# H17R10.net
KiCad netlist of a schematic drawn in EAGLE
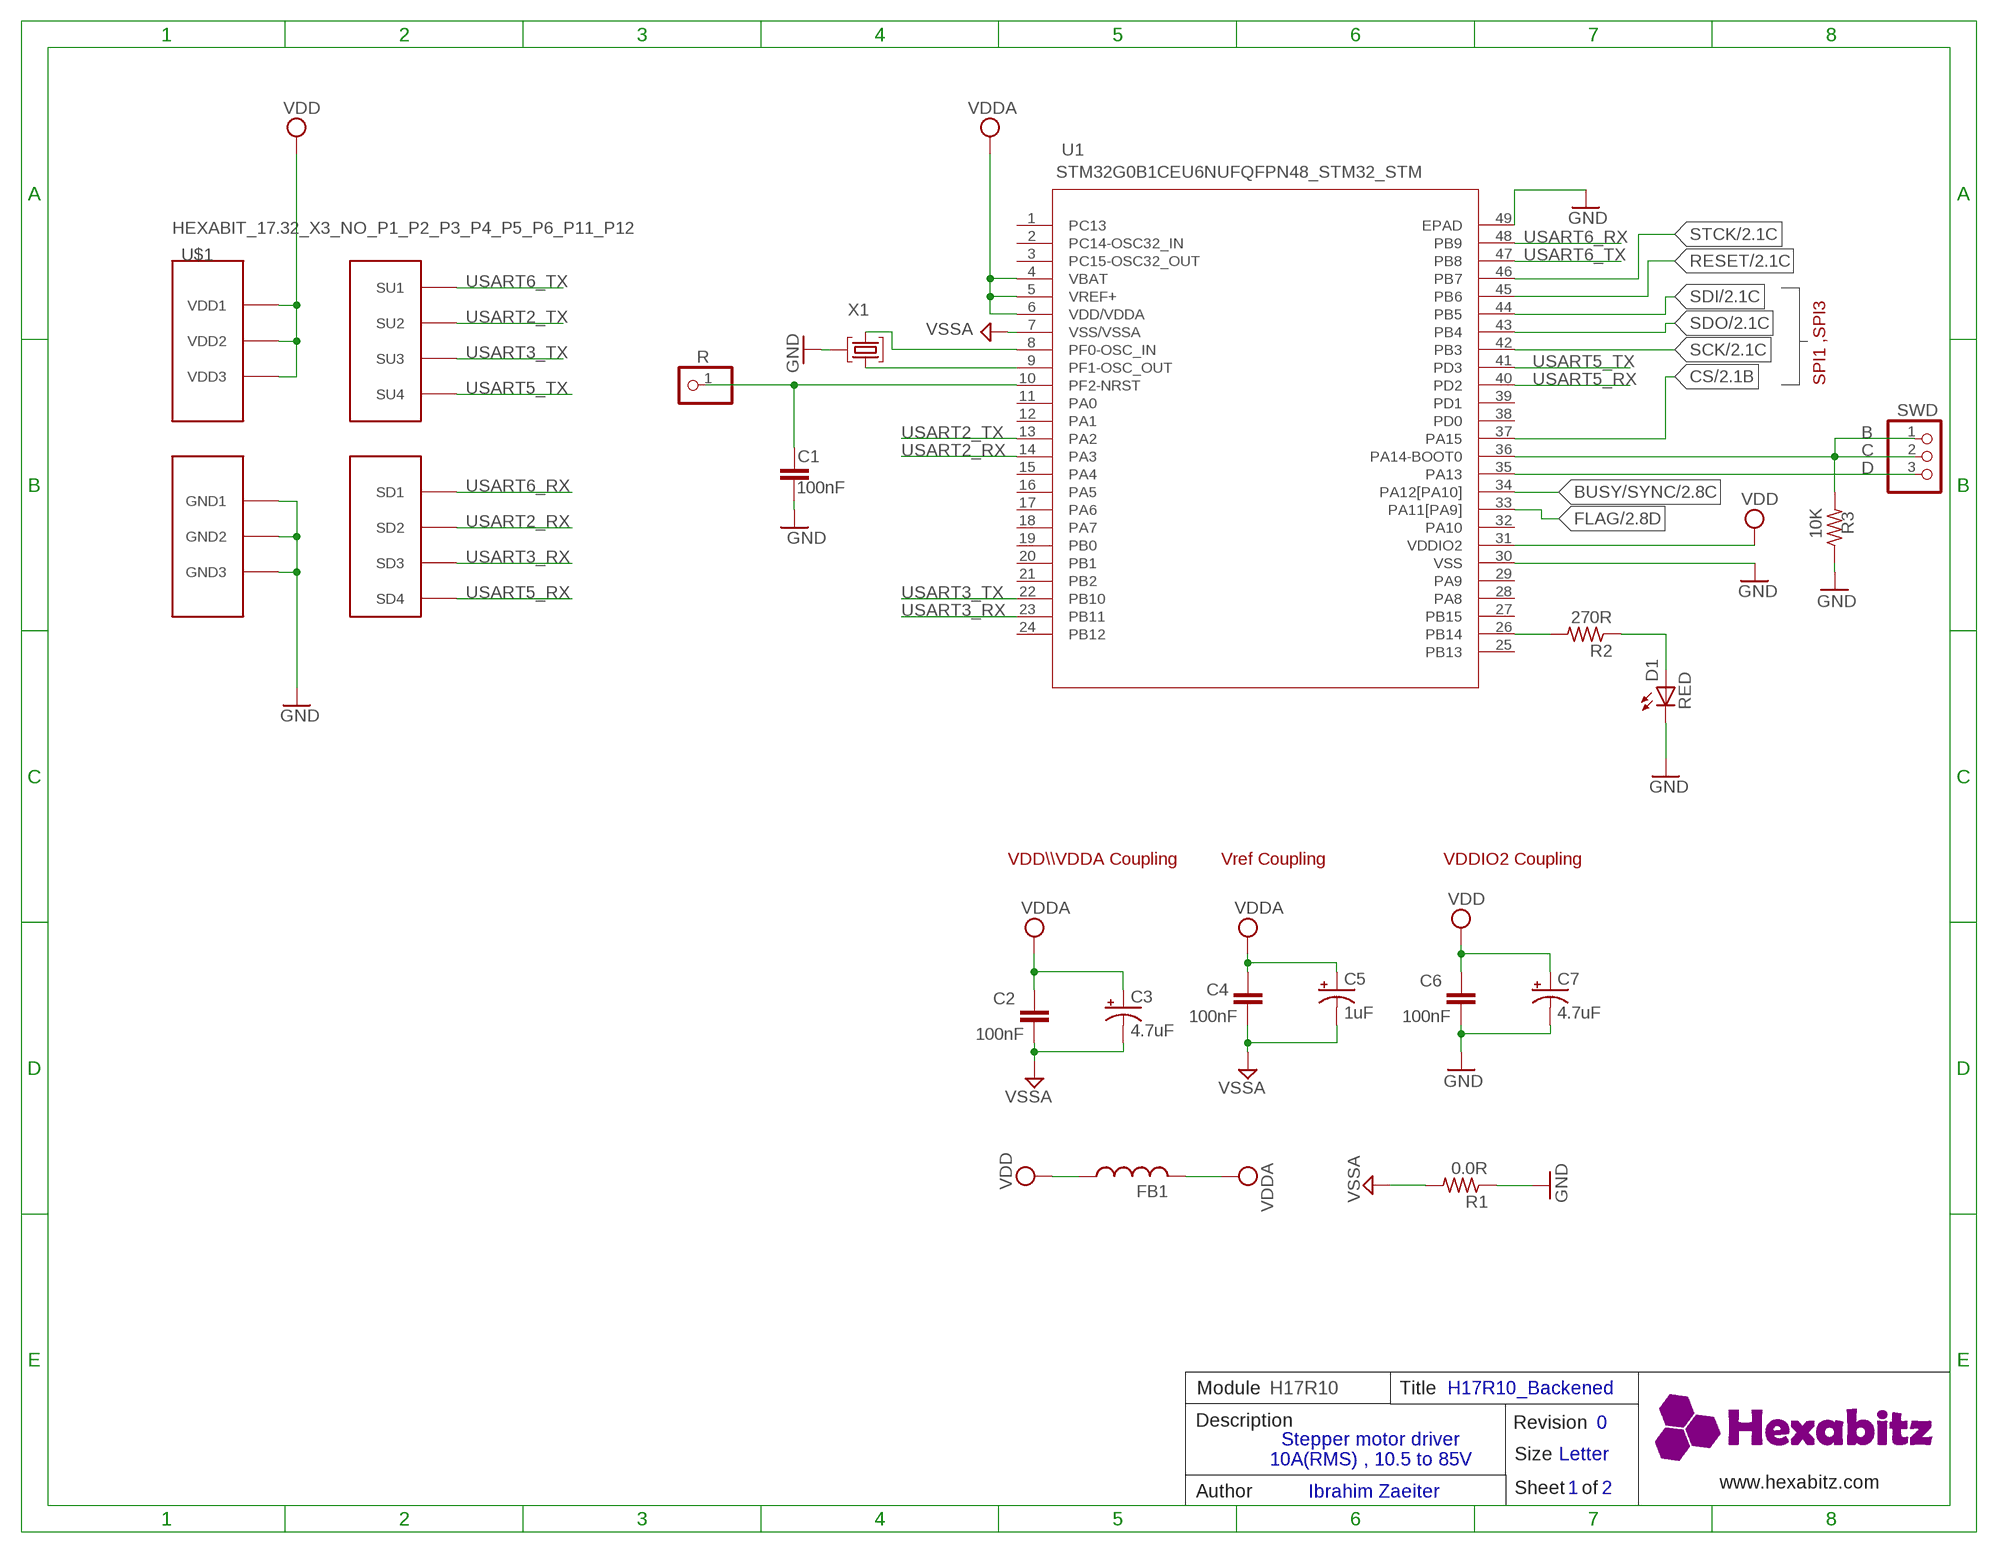
[diagram p0: schematic, sheet 1]
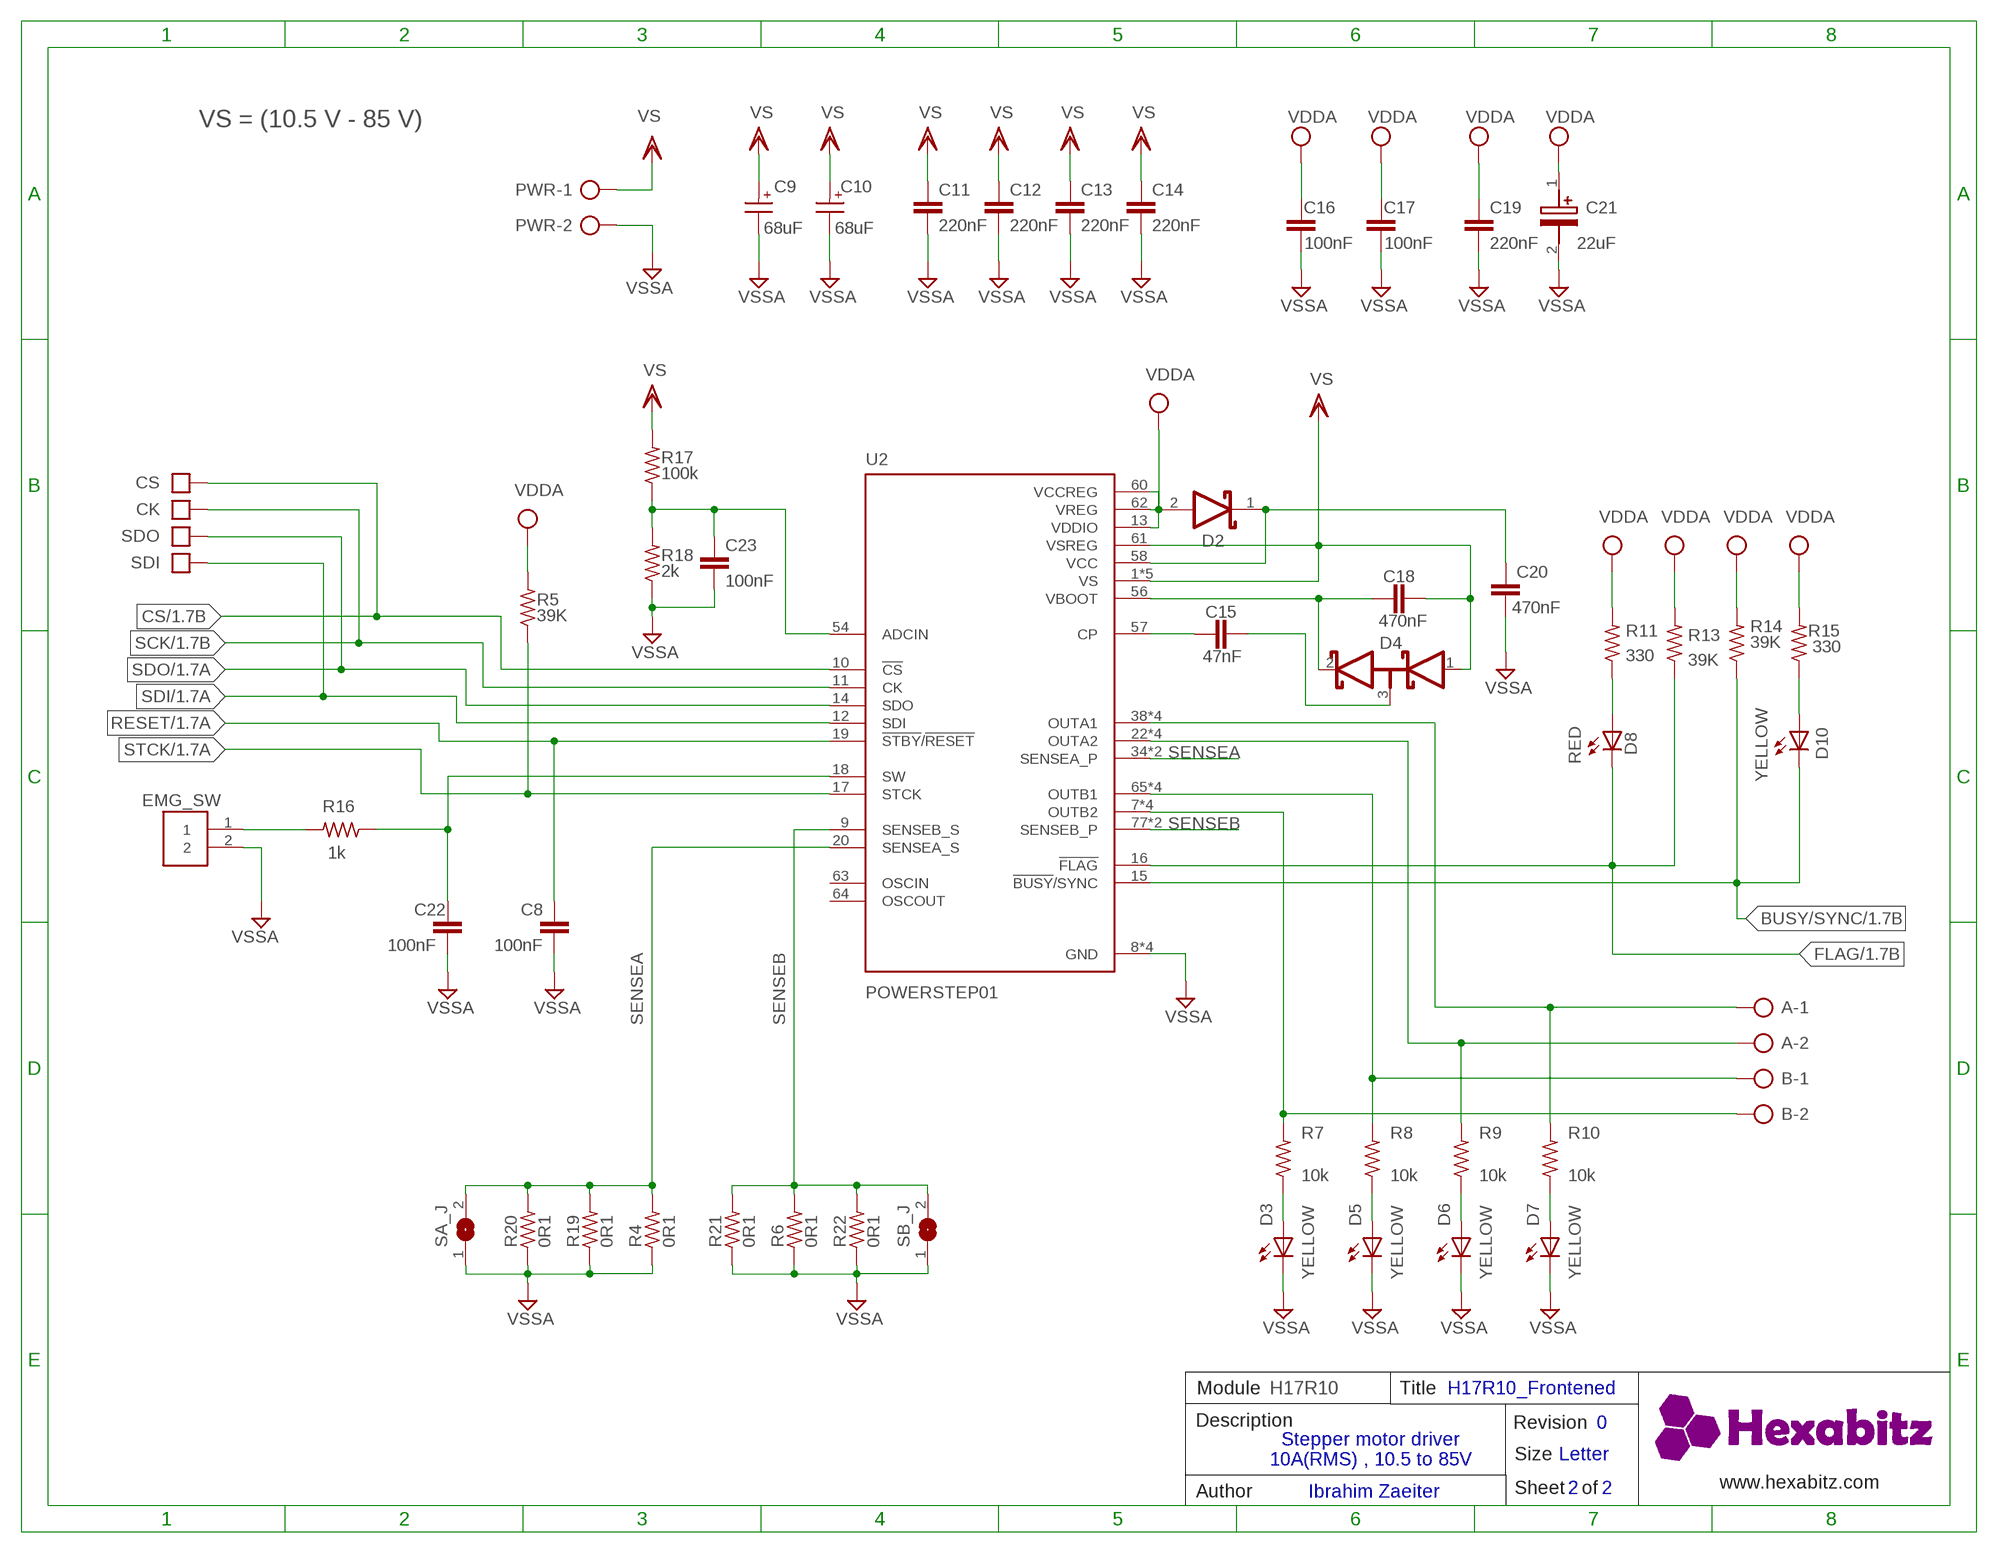
[diagram p1: schematic, sheet 2]

(export (version "E")
  (design (tool "Eeschema 10.0.6"))
  (components
    (comp (ref "A")
      (value "AK500/2")
      (footprint "eagle-import:AK500_2")
      (fields (field (name "MPN") "282836-2"))
      (libsource (lib "eagle-import") (part "AK500/2"))
    )
    (comp (ref "B")
      (value "AK500/2")
      (footprint "eagle-import:AK500_2")
      (fields (field (name "MPN") "282836-2"))
      (libsource (lib "eagle-import") (part "AK500/2"))
    )
    (comp (ref "C8")
      (value "100nF")
      (footprint "eagle-import:C-0603")
      (fields
        (field (name "CAPACITANCE") "100nF")
        (field (name "MFN") "TDK CORPORATION")
        (field (name "MPN") "C1608X7R1H104K080AA")
        (field (name "OCTOPART_URL") "https://octopart.com/c1608x7r1h104k080aa-tdk-25947665?r=sp")
      )
      (libsource (lib "eagle-import") (part "C-0603"))
    )
    (comp (ref "C9")
      (value "68uF")
      (footprint "eagle-import:WCAP-ASLI_12.5X14(DXL)")
      (fields (field (name "MPN") "EEVFK2A680Q"))
      (libsource (lib "eagle-import") (part "WCAP-ASLI_12.5X14EEVFK2A680Q"))
    )
    (comp (ref "C10")
      (value "68uF")
      (footprint "eagle-import:WCAP-ASLI_12.5X14(DXL)")
      (fields (field (name "MPN") "EEVFK2A680Q"))
      (libsource (lib "eagle-import") (part "WCAP-ASLI_12.5X14EEVFK2A680Q"))
    )
    (comp (ref "C11")
      (value "220nF")
      (footprint "eagle-import:C-0805")
      (libsource (lib "eagle-import") (part "C-0805"))
    )
    (comp (ref "C12")
      (value "220nF")
      (footprint "eagle-import:C-0805")
      (libsource (lib "eagle-import") (part "C-0805"))
    )
    (comp (ref "C13")
      (value "220nF")
      (footprint "eagle-import:C-0805")
      (libsource (lib "eagle-import") (part "C-0805"))
    )
    (comp (ref "C14")
      (value "220nF")
      (footprint "eagle-import:C-0805")
      (libsource (lib "eagle-import") (part "C-0805"))
    )
    (comp (ref "C15")
      (value "47nF")
      (footprint "eagle-import:C-0805")
      (fields
        (field (name "MFN") "KEMET")
        (field (name "MPN") "C0805C473K1RACTU")
        (field (name "OCTOPART_URL") "https://octopart.com/c0805c473k1ractu-kemet-12557765?r=sp")
        (field (name "VOLTAGE_RATING") "100V")
      )
      (libsource (lib "eagle-import") (part "C-0805"))
    )
    (comp (ref "C16")
      (value "100nF")
      (footprint "eagle-import:C-0603")
      (fields
        (field (name "CAPACITANCE") "100nF")
        (field (name "MFN") "AVX CORPORATION")
        (field (name "MPN") "'0603YC104K4T2A")
        (field (name "OCTOPART_URL") "'https://octopart.com/0603yc104k4t2a-avx+interconnect+%2F+elco-8120651")
        (field (name "TOLERANCE") "10%")
        (field (name "VOLTAGE_RATING") "16.0 V")
      )
      (libsource (lib "eagle-import") (part "C-0603"))
    )
    (comp (ref "C17")
      (value "100nF")
      (footprint "eagle-import:C-0603")
      (fields
        (field (name "CAPACITANCE") "100nF")
        (field (name "MFN") "AVX CORPORATION")
        (field (name "MPN") "'0603YC104K4T2A")
        (field (name "OCTOPART_URL") "'https://octopart.com/0603yc104k4t2a-avx+interconnect+%2F+elco-8120651")
        (field (name "TOLERANCE") "10%")
        (field (name "VOLTAGE_RATING") "16.0 V")
      )
      (libsource (lib "eagle-import") (part "C-0603"))
    )
    (comp (ref "C18")
      (value "470nF")
      (footprint "eagle-import:C-0603")
      (fields
        (field (name "MFN") "TDK")
        (field (name "MPN") "CGA3E3X7R1E474K080AE")
        (field (name "OCTOPART_URL") "https://octopart.com/search?q=CAP+CER+470nF+25V+X7R+0603&currency=USD&specs=0")
        (field (name "VOLTAGE_RATING") "100V")
      )
      (libsource (lib "eagle-import") (part "C-0603"))
    )
    (comp (ref "C19")
      (value "220nF")
      (footprint "eagle-import:C-0603")
      (fields
        (field (name "MFN") "TDK")
        (field (name "MPN") "CGA3E3X7R1V224K080AE")
        (field (name "OCTOPART_URL") "https://octopart.com/cga3e3x7r1v224k080ae-tdk-68305867?r=sp")
      )
      (libsource (lib "eagle-import") (part "C-0603"))
    )
    (comp (ref "C20")
      (value "470nF")
      (footprint "eagle-import:C-0603")
      (fields
        (field (name "MFN") "TDK")
        (field (name "MPN") "CGA3E3X7R1E474K080AE")
        (field (name "OCTOPART_URL") "https://octopart.com/search?q=CAP+CER+470nF+25V+X7R+0603&currency=USD&specs=0")
        (field (name "VOLTAGE_RATING") "100V")
      )
      (libsource (lib "eagle-import") (part "C-0603"))
    )
    (comp (ref "C21")
      (value "22uF")
      (footprint "eagle-import:T491A")
      (fields
        (field (name "MANUFACTURER_PART_NUMBER") "T491A226K006AT")
        (field (name "MOUSER_PART_NUMBER") "80-T491A226K006")
      )
      (libsource (lib "eagle-import") (part "T491A226K006AT"))
    )
    (comp (ref "C22")
      (value "100nF")
      (footprint "eagle-import:C-0603")
      (fields
        (field (name "CAPACITANCE") "100nF")
        (field (name "MFN") "TDK CORPORATION")
        (field (name "MPN") "C1608X7R1H104K080AA")
        (field (name "OCTOPART_URL") "https://octopart.com/c1608x7r1h104k080aa-tdk-25947665?r=sp")
      )
      (libsource (lib "eagle-import") (part "C-0603"))
    )
    (comp (ref "C23")
      (value "100nF")
      (footprint "eagle-import:C-0603")
      (fields
        (field (name "CAPACITANCE") "100nF")
        (field (name "MFN") "TDK CORPORATION")
        (field (name "MPN") "C1608X7R1H104K080AA")
        (field (name "OCTOPART_URL") "https://octopart.com/c1608x7r1h104k080aa-tdk-25947665?r=sp")
      )
      (libsource (lib "eagle-import") (part "C-0603"))
    )
    (comp (ref "CK")
      (value "PAD4")
      (footprint "eagle-import:PAD4")
      (libsource (lib "eagle-import") (part "PAD4"))
    )
    (comp (ref "CS")
      (value "PAD4")
      (footprint "eagle-import:PAD4")
      (libsource (lib "eagle-import") (part "PAD4"))
    )
    (comp (ref "D2")
      (value "STMICROELECTRONICS_BAT46ZFILMSTMICROELECTRONICS_BAT46ZFILM_0_3")
      (footprint "eagle-import:STMICROELECTRONICS_BAT46ZFILM_3")
      (fields (field (name "MPN") "BAT46ZFILM"))
      (libsource (lib "eagle-import") (part "STMICROELECTRONICS_BAT46ZFILMSTMICROELECTRONICS_BAT46ZFILM_0_3"))
    )
    (comp (ref "D3")
      (value "YELLOW")
      (footprint "eagle-import:VLMY1300-GS08")
      (fields
        (field (name "MPN") "VLMY1300-GS08")
        (field (name "MFN") "Lite-On")
        (field (name "MPN_1") "LTST-C170YKT")
        (field (name "OCTOPART_URL") "https://octopart.com/ltst-c170ykt-lite-on-549813?r=sp")
      )
      (libsource (lib "eagle-import") (part "VLMY1300-GS08"))
    )
    (comp (ref "D4")
      (value "STMICROELECTRONICS_BAR43SFILMSTMICROELECTRONICS_BAR43SFILM_0_0")
      (footprint "eagle-import:STMICROELECTRONICS_BAR43SFILM_0")
      (fields (field (name "MPN") "BAR43SFILM"))
      (libsource (lib "eagle-import") (part "STMICROELECTRONICS_BAR43SFILMSTMICROELECTRONICS_BAR43SFILM_0_0"))
    )
    (comp (ref "D5")
      (value "YELLOW")
      (footprint "eagle-import:VLMY1300-GS08")
      (fields
        (field (name "MPN") "VLMY1300-GS08")
        (field (name "MFN") "Lite-On")
        (field (name "MPN_1") "LTST-C170YKT")
        (field (name "OCTOPART_URL") "https://octopart.com/ltst-c170ykt-lite-on-549813?r=sp")
      )
      (libsource (lib "eagle-import") (part "VLMY1300-GS08"))
    )
    (comp (ref "D6")
      (value "YELLOW")
      (footprint "eagle-import:VLMY1300-GS08")
      (fields
        (field (name "MPN") "VLMY1300-GS08")
        (field (name "MFN") "Lite-On")
        (field (name "MPN_1") "LTST-C170YKT")
        (field (name "OCTOPART_URL") "https://octopart.com/ltst-c170ykt-lite-on-549813?r=sp")
      )
      (libsource (lib "eagle-import") (part "VLMY1300-GS08"))
    )
    (comp (ref "D7")
      (value "YELLOW")
      (footprint "eagle-import:VLMY1300-GS08")
      (fields
        (field (name "MPN") "VLMY1300-GS08")
        (field (name "MFN") "Lite-On")
        (field (name "MPN_1") "LTST-C170YKT")
        (field (name "OCTOPART_URL") "https://octopart.com/ltst-c170ykt-lite-on-549813?r=sp")
      )
      (libsource (lib "eagle-import") (part "VLMY1300-GS08"))
    )
    (comp (ref "D8")
      (value "RED")
      (footprint "eagle-import:VLMS1300-GS08")
      (fields
        (field (name "MPN") "VLMS1300-GS08")
        (field (name "MFN") "Lite-On")
        (field (name "MPN_1") "LTST-C170-EKT")
        (field (name "OCTOPART_URL") "https://octopart.com/ltst-c170ekt-lite-on-549816?r=sp")
      )
      (libsource (lib "eagle-import") (part "VLMS1300-GS08"))
    )
    (comp (ref "D10")
      (value "YELLOW")
      (footprint "eagle-import:VLMY1300-GS08")
      (fields
        (field (name "MPN") "VLMY1300-GS08")
        (field (name "MFN") "Lite-On")
        (field (name "MPN_1") "LTST-C170YKT")
        (field (name "OCTOPART_URL") "https://octopart.com/ltst-c170ykt-lite-on-549813?r=sp")
      )
      (libsource (lib "eagle-import") (part "VLMY1300-GS08"))
    )
    (comp (ref "EMG_SW")
      (value "3-644456-2")
      (footprint "eagle-import:TE_3-644456-2")
      (fields (field (name "MF") "TE Connectivity") (field (name "MPN") "87224-1"))
      (libsource (lib "eagle-import") (part "3-644456-2"))
    )
    (comp (ref "PWR")
      (value "AK500/2")
      (footprint "eagle-import:AK500_2")
      (fields (field (name "MPN") "282836-2"))
      (libsource (lib "eagle-import") (part "AK500/2"))
    )
    (comp (ref "R4")
      (value "0R1")
      (footprint "eagle-import:R2512")
      (fields (field (name "MPN") "PE2512FKE7W0R1L"))
      (libsource (lib "eagle-import") (part "R-US_R2512"))
    )
    (comp (ref "R5")
      (value "39K")
      (footprint "eagle-import:R-0603")
      (fields
        (field (name "MFN") "Yageo")
        (field (name "MPN") "RC0603FR-0739KL")
        (field (name "OCTOPART_URL") "https://octopart.com/rc0603fr-0739kl-yageo-55402883?r=sp")
        (field (name "RESISTANCE") "39K")
      )
      (libsource (lib "eagle-import") (part "R-0603"))
    )
    (comp (ref "R6")
      (value "0R1")
      (footprint "eagle-import:R2512")
      (fields (field (name "MPN") "PE2512FKE7W0R1L"))
      (libsource (lib "eagle-import") (part "R-US_R2512"))
    )
    (comp (ref "R7")
      (value "10k")
      (footprint "eagle-import:R-0805")
      (fields
        (field (name "MFN") "Panasonic")
        (field (name "MPN") "ERJ-6GEYJ103V")
        (field (name "OCTOPART_URL") "https://octopart.com/erj-6geyj103v-panasonic-55422885?r=sp")
      )
      (libsource (lib "eagle-import") (part "R-0805"))
    )
    (comp (ref "R8")
      (value "10k")
      (footprint "eagle-import:R-0805")
      (fields
        (field (name "MFN") "Panasonic")
        (field (name "MPN") "ERJ-6GEYJ103V")
        (field (name "OCTOPART_URL") "https://octopart.com/erj-6geyj103v-panasonic-55422885?r=sp")
      )
      (libsource (lib "eagle-import") (part "R-0805"))
    )
    (comp (ref "R9")
      (value "10k")
      (footprint "eagle-import:R-0805")
      (fields
        (field (name "MFN") "Panasonic")
        (field (name "MPN") "ERJ-6GEYJ103V")
        (field (name "OCTOPART_URL") "https://octopart.com/erj-6geyj103v-panasonic-55422885?r=sp")
      )
      (libsource (lib "eagle-import") (part "R-0805"))
    )
    (comp (ref "R10")
      (value "10k")
      (footprint "eagle-import:R-0805")
      (fields
        (field (name "MFN") "Panasonic")
        (field (name "MPN") "ERJ-6GEYJ103V")
        (field (name "OCTOPART_URL") "https://octopart.com/erj-6geyj103v-panasonic-55422885?r=sp")
      )
      (libsource (lib "eagle-import") (part "R-0805"))
    )
    (comp (ref "R11")
      (value "330")
      (footprint "eagle-import:R-0603")
      (fields
        (field (name "MFN") "Yageo")
        (field (name "MPN") "RC0603JR-07330RL")
        (field (name "OCTOPART_URL") "https://octopart.com/rc0603jr-07330rl-yageo-39803615?r=sp")
        (field (name "RESISTANCE") "330")
      )
      (libsource (lib "eagle-import") (part "R-0603"))
    )
    (comp (ref "R13")
      (value "39K")
      (footprint "eagle-import:R-0603")
      (fields
        (field (name "MFN") "Yageo")
        (field (name "MPN") "RC0603FR-0739KL")
        (field (name "OCTOPART_URL") "https://octopart.com/rc0603fr-0739kl-yageo-55402883?r=sp")
        (field (name "RESISTANCE") "39K")
      )
      (libsource (lib "eagle-import") (part "R-0603"))
    )
    (comp (ref "R14")
      (value "39K")
      (footprint "eagle-import:R-0603")
      (fields
        (field (name "MFN") "Yageo")
        (field (name "MPN") "RC0603FR-0739KL")
        (field (name "OCTOPART_URL") "https://octopart.com/rc0603fr-0739kl-yageo-55402883?r=sp")
        (field (name "RESISTANCE") "39K")
      )
      (libsource (lib "eagle-import") (part "R-0603"))
    )
    (comp (ref "R15")
      (value "330")
      (footprint "eagle-import:R-0603")
      (fields
        (field (name "MFN") "Yageo")
        (field (name "MPN") "RC0603JR-07330RL")
        (field (name "OCTOPART_URL") "https://octopart.com/rc0603jr-07330rl-yageo-39803615?r=sp")
        (field (name "RESISTANCE") "330")
      )
      (libsource (lib "eagle-import") (part "R-0603"))
    )
    (comp (ref "R16")
      (value "1k")
      (footprint "eagle-import:R-0603")
      (fields
        (field (name "MFN") "Yageo")
        (field (name "MPN") "RC0603JR-07330RL")
        (field (name "OCTOPART_URL") "https://octopart.com/rc0603jr-07330rl-yageo-39803615?r=sp")
        (field (name "RESISTANCE") "330")
      )
      (libsource (lib "eagle-import") (part "R-0603"))
    )
    (comp (ref "R17")
      (value "100k")
      (footprint "eagle-import:R-0603")
      (fields
        (field (name "MFN") "Yageo")
        (field (name "MPN") "RC0603FR-0739KL")
        (field (name "OCTOPART_URL") "https://octopart.com/rc0603fr-0739kl-yageo-55402883?r=sp")
        (field (name "RESISTANCE") "39K")
      )
      (libsource (lib "eagle-import") (part "R-0603"))
    )
    (comp (ref "R18")
      (value "2k")
      (footprint "eagle-import:R-0603")
      (fields
        (field (name "MFN") "Yageo")
        (field (name "MPN") "RC0603FR-0739KL")
        (field (name "OCTOPART_URL") "https://octopart.com/rc0603fr-0739kl-yageo-55402883?r=sp")
        (field (name "RESISTANCE") "39K")
      )
      (libsource (lib "eagle-import") (part "R-0603"))
    )
    (comp (ref "R19")
      (value "0R1")
      (footprint "eagle-import:R2512")
      (fields (field (name "MPN") "PE2512FKE7W0R1L"))
      (libsource (lib "eagle-import") (part "R-US_R2512"))
    )
    (comp (ref "R20")
      (value "0R1")
      (footprint "eagle-import:R2512")
      (fields (field (name "MPN") "PE2512FKE7W0R1L"))
      (libsource (lib "eagle-import") (part "R-US_R2512"))
    )
    (comp (ref "R21")
      (value "0R1")
      (footprint "eagle-import:R2512")
      (fields (field (name "MPN") "PE2512FKE7W0R1L"))
      (libsource (lib "eagle-import") (part "R-US_R2512"))
    )
    (comp (ref "R22")
      (value "0R1")
      (footprint "eagle-import:R2512")
      (fields (field (name "MPN") "PE2512FKE7W0R1L"))
      (libsource (lib "eagle-import") (part "R-US_R2512"))
    )
    (comp (ref "SA_J")
      (value "SJW")
      (footprint "eagle-import:SJW")
      (libsource (lib "eagle-import") (part "SJW"))
    )
    (comp (ref "SB_J")
      (value "SJW")
      (footprint "eagle-import:SJW")
      (libsource (lib "eagle-import") (part "SJW"))
    )
    (comp (ref "SDI")
      (value "PAD4")
      (footprint "eagle-import:PAD4")
      (libsource (lib "eagle-import") (part "PAD4"))
    )
    (comp (ref "SDO")
      (value "PAD4")
      (footprint "eagle-import:PAD4")
      (libsource (lib "eagle-import") (part "PAD4"))
    )
    (comp (ref "U2")
      (value "POWERSTEP01")
      (footprint "eagle-import:IC_POWERSTEP01")
      (fields (field (name "MF") "STMicroelectronics"))
      (libsource (lib "eagle-import") (part "POWERSTEP01"))
    )
    (comp (ref "C1")
      (value "100nF")
      (footprint "eagle-import:C-0603")
      (fields
        (field (name "CAPACITANCE") "100nF")
        (field (name "MFN") "AVX CORPORATION")
        (field (name "MPN") "0603YC104K4T2A")
        (field (name "OCTOPART_URL") "'https://octopart.com/0603yc104k4t2a-avx+interconnect+%2F+elco-8120651")
        (field (name "TOLERANCE") "10%")
        (field (name "VOLTAGE_RATING") "16.0 V")
      )
      (libsource (lib "eagle-import") (part "C-0603"))
    )
    (comp (ref "C2")
      (value "100nF")
      (footprint "eagle-import:C-0603")
      (fields
        (field (name "CAPACITANCE") "100nF")
        (field (name "MFN") "AVX CORPORATION")
        (field (name "MPN") "'0603YC104K4T2A")
        (field (name "OCTOPART_URL") "'https://octopart.com/0603yc104k4t2a-avx+interconnect+%2F+elco-8120651")
        (field (name "TOLERANCE") "10%")
        (field (name "VOLTAGE_RATING") "16.0 V")
      )
      (libsource (lib "eagle-import") (part "C-0603"))
    )
    (comp (ref "C3")
      (value "4.7uF")
      (footprint "eagle-import:C-0805-POL")
      (fields
        (field (name "CAPACITANCE") "4.7uF")
        (field (name "MFN") "'Panasonic")
        (field (name "MPN") "'10TPU4R7MSI")
        (field (name "OCTOPART_URL") "https://octopart.com/10tpu4r7msi-panasonic-29487748?r=sp")
        (field (name "TOLERANCE") "20%")
        (field (name "VOLTAGE_RATING") "10.0 V")
      )
      (libsource (lib "eagle-import") (part "C-0805-POL"))
    )
    (comp (ref "C4")
      (value "100nF")
      (footprint "eagle-import:C-0603")
      (fields
        (field (name "CAPACITANCE") "100nF")
        (field (name "MFN") "AVX CORPORATION")
        (field (name "MPN") "'0603YC104K4T2A")
        (field (name "OCTOPART_URL") "'https://octopart.com/0603yc104k4t2a-avx+interconnect+%2F+elco-8120651")
        (field (name "TOLERANCE") "10%")
        (field (name "VOLTAGE_RATING") "16.0 V")
      )
      (libsource (lib "eagle-import") (part "C-0603"))
    )
    (comp (ref "C5")
      (value "1uF")
      (footprint "eagle-import:C-0805-POL")
      (fields
        (field (name "CAPACITANCE") "4.7uF")
        (field (name "MFN") "'YAGEO [VA]")
        (field (name "MPN") "'CC0805KKX7R7BB105")
        (field (name "OCTOPART_URL") "'https://octopart.com/cc0805kkx7r7bb105-yageo-8376555?r=sp")
        (field (name "TOLERANCE") "20%")
        (field (name "VOLTAGE_RATING") "10.0 V")
      )
      (libsource (lib "eagle-import") (part "C-0805-POL"))
    )
    (comp (ref "C6")
      (value "100nF")
      (footprint "eagle-import:C-0603")
      (fields
        (field (name "CAPACITANCE") "100nF")
        (field (name "MFN") "AVX CORPORATION")
        (field (name "MPN") "'0603YC104K4T2A")
        (field (name "OCTOPART_URL") "'https://octopart.com/0603yc104k4t2a-avx+interconnect+%2F+elco-8120651")
        (field (name "TOLERANCE") "10%")
        (field (name "VOLTAGE_RATING") "16.0 V")
      )
      (libsource (lib "eagle-import") (part "C-0603"))
    )
    (comp (ref "C7")
      (value "4.7uF")
      (footprint "eagle-import:C-0805-POL")
      (fields
        (field (name "CAPACITANCE") "1.00uF")
        (field (name "MFN") "'Panasonic")
        (field (name "MPN") "'10TPU4R7MSI")
        (field (name "OCTOPART_URL") "https://octopart.com/10tpu4r7msi-panasonic-29487748?r=sp")
        (field (name "TOLERANCE") "10%")
        (field (name "VOLTAGE_RATING") "16.0 V")
      )
      (libsource (lib "eagle-import") (part "C-0805-POL"))
    )
    (comp (ref "D1")
      (value "RED")
      (footprint "eagle-import:VLMS1300-GS08")
      (fields (field (name "MPN") "VLMS1300-GS08"))
      (libsource (lib "eagle-import") (part "VLMS1300-GS08"))
    )
    (comp (ref "FB1")
      (value "FB-TDK_MMZ1608Y300B")
      (footprint "eagle-import:FB-TDK_MMZ1608Y300B")
      (fields
        (field (name "MFN") "TDK ")
        (field (name "MPN") "MMZ1608Y300BTA00")
        (field (name "OCTOPART_URL") "https://octopart.com/mmz1608y300bta00-tdk-7906990?r=sp")
      )
      (libsource (lib "eagle-import") (part "FB-TDK_MMZ1608Y300B"))
    )
    (comp (ref "R")
      (value "PINHD-1X1")
      (footprint "eagle-import:1X01")
      (fields (field (name "MPN") "87227-1"))
      (libsource (lib "eagle-import") (part "PINHD-1X1"))
    )
    (comp (ref "R1")
      (value "0.0R")
      (footprint "eagle-import:R-0603")
      (fields
        (field (name "MFN") "YAGEO [VR]")
        (field (name "MPN") "RC0603JR-070RL")
        (field (name "OCTOPART_URL") "https://octopart.com/rc0603jr-070rl-yageo-1241539?r=sp")
        (field (name "RESISTANCE") "0R")
      )
      (libsource (lib "eagle-import") (part "R-0603"))
    )
    (comp (ref "R2")
      (value "270R")
      (footprint "eagle-import:R-0603")
      (fields
        (field (name "MFN") "'Panasonic")
        (field (name "MPN") "'ERJ-3GEYJ271V")
        (field (name "OCTOPART_URL") "https://octopart.com/erj-3geyj271v-panasonic-55560546?r=sp")
        (field (name "RESISTANCE") "270R")
      )
      (libsource (lib "eagle-import") (part "R-0603"))
    )
    (comp (ref "R3")
      (value "10K")
      (footprint "eagle-import:R-0603")
      (fields
        (field (name "MFN") "Vishay")
        (field (name "MPN") "'060300J0103T5E")
        (field (name "OCTOPART_URL") "https://octopart.com/search?q=060300J0103T5E&currency=USD&specs=0")
        (field (name "RESISTANCE") "10K")
      )
      (libsource (lib "eagle-import") (part "R-0603"))
    )
    (comp (ref "SWD")
      (value "PINHD-1X3")
      (footprint "eagle-import:1X03")
      (libsource (lib "eagle-import") (part "PINHD-1X3"))
    )
    (comp (ref "U$1")
      (value "HEXABIT_17.32_X3_NO_P1_P2_P3_P4_P5_P6_P11_P12")
      (footprint "eagle-import:HEXABIT_17.32_X3_NO_P1_P2_P3_P4_P5_P6_P11_P12")
      (libsource (lib "eagle-import") (part "HEXABIT_17.32_X3_NO_P1_P2_P3_P4_P5_P6_P11_P12"))
    )
    (comp (ref "U1")
      (value "STM32G0B1CEU6NUFQFPN48_STM32_STM")
      (footprint "eagle-import:HEXABITZ_ICS_UFQFPN48_STM32_STM")
      (fields
        (field (name "MPN") "STM32G0B1CEU6N")
        (field (name "OCTOPART_URL") "https://octopart.com/stm32g0b1ceu6n-stmicroelectronics-116364672?r=sp")
        (field (name "COPYRIGHT") "Copyright (C) 2022 Ultra Librarian. All rights reserved.")
      )
      (libsource (lib "eagle-import") (part "STM32G0B1CEU6NUFQFPN48_STM32_STM"))
    )
    (comp (ref "X1")
      (value "8MHZ")
      (footprint "eagle-import:XTALL_CSTCE8M00G52")
      (fields
        (field (name "MPN") "CSTCE8M00G52Z-R0")
        (field (name "MPN_1") "CSTNE8M00G550000R0")
        (field (name "OCTOPART_URL") "https://octopart.com/cstne8m00g550000r0-murata-91406934?r=sp")
      )
      (libsource (lib "eagle-import") (part "XTALL_CSTCE8M00G52"))
    )
  )
  (nets
    (net (code "1") (name "BUSY{slash}SYNC") (class "Default")
      (node (ref "D10") (pin "C") (pinfunction "C_C") (pintype "passive"))
      (node (ref "R14") (pin "1") (pinfunction "1_1") (pintype "passive"))
      (node (ref "U1") (pin "34") (pinfunction "PA12[PA10]_34") (pintype "bidirectional"))
      (node (ref "U2") (pin "15") (pinfunction "~{BUSY}/SYNC_15") (pintype "output"))
    )
    (net (code "2") (name "C") (class "Default")
      (node (ref "R3") (pin "2") (pinfunction "2_2") (pintype "passive"))
      (node (ref "SWD") (pin "1") (pinfunction "1_1") (pintype "passive"))
      (node (ref "SWD") (pin "2") (pinfunction "2_2") (pintype "passive"))
      (node (ref "U1") (pin "36") (pinfunction "PA14-BOOT0_36") (pintype "bidirectional"))
    )
    (net (code "3") (name "CS") (class "Default")
      (node (ref "CS") (pin "P$1") (pinfunction "P$1_P$1") (pintype "passive"))
      (node (ref "U1") (pin "37") (pinfunction "PA15_37") (pintype "bidirectional"))
      (node (ref "U2") (pin "10") (pinfunction "~{CS}_10") (pintype "input"))
    )
    (net (code "4") (name "D") (class "Default")
      (node (ref "SWD") (pin "3") (pinfunction "3_3") (pintype "passive"))
      (node (ref "U1") (pin "35") (pinfunction "PA13_35") (pintype "bidirectional"))
    )
    (net (code "5") (name "FLAG") (class "Default")
      (node (ref "D8") (pin "C") (pinfunction "C_C") (pintype "passive"))
      (node (ref "R13") (pin "1") (pinfunction "1_1") (pintype "passive"))
      (node (ref "U1") (pin "33") (pinfunction "PA11[PA9]_33") (pintype "bidirectional"))
      (node (ref "U2") (pin "16") (pinfunction "~{FLAG}_16") (pintype "output"))
    )
    (net (code "6") (name "GND") (class "Default")
      (node (ref "C1") (pin "1") (pinfunction "1_1") (pintype "passive"))
      (node (ref "C6") (pin "1") (pinfunction "1_1") (pintype "passive"))
      (node (ref "C7") (pin "2") (pinfunction "-_2") (pintype "passive"))
      (node (ref "D1") (pin "C") (pinfunction "C_C") (pintype "passive"))
      (node (ref "R1") (pin "1") (pinfunction "1_1") (pintype "passive"))
      (node (ref "R3") (pin "1") (pinfunction "1_1") (pintype "passive"))
      (node (ref "U$1") (pin "PAD_PD12") (pinfunction "GND1_PAD_PD12") (pintype "power_in"))
      (node (ref "U$1") (pin "PAD_PD17") (pinfunction "GND2_PAD_PD17") (pintype "power_in"))
      (node (ref "U$1") (pin "PAD_PD19") (pinfunction "GND3_PAD_PD19") (pintype "power_in"))
      (node (ref "U1") (pin "30") (pinfunction "VSS_30") (pintype "passive"))
      (node (ref "U1") (pin "49") (pinfunction "EPAD_49") (pintype "passive"))
      (node (ref "X1") (pin "P$2") (pinfunction "2_P$2") (pintype "passive"))
    )
    (net (code "7") (name "Net-(AA-KL)") (class "Default")
      (node (ref "A") (pin "1") (pinfunction "KL_1") (pintype "passive"))
      (node (ref "R9") (pin "2") (pinfunction "2_2") (pintype "passive"))
      (node (ref "U2") (pin "22") (pinfunction "OUTA2_22") (pintype "output"))
      (node (ref "U2") (pin "33") (pinfunction "OUTA2_33") (pintype "output"))
      (node (ref "U2") (pin "37") (pinfunction "OUTA2_37") (pintype "output"))
      (node (ref "U2") (pin "EPAD3") (pinfunction "OUTA2_EPAD3") (pintype "output"))
    )
    (net (code "8") (name "Net-(AB-KL)") (class "Default")
      (node (ref "A") (pin "2") (pinfunction "KL_2") (pintype "passive"))
      (node (ref "R10") (pin "2") (pinfunction "2_2") (pintype "passive"))
      (node (ref "U2") (pin "38") (pinfunction "OUTA1_38") (pintype "output"))
      (node (ref "U2") (pin "42") (pinfunction "OUTA1_42") (pintype "output"))
      (node (ref "U2") (pin "53") (pinfunction "OUTA1_53") (pintype "output"))
      (node (ref "U2") (pin "EPAD4") (pinfunction "OUTA1_EPAD4") (pintype "output"))
    )
    (net (code "9") (name "Net-(BA-KL)") (class "Default")
      (node (ref "B") (pin "1") (pinfunction "KL_1") (pintype "passive"))
      (node (ref "R8") (pin "2") (pinfunction "2_2") (pintype "passive"))
      (node (ref "U2") (pin "65") (pinfunction "OUTB1_65") (pintype "output"))
      (node (ref "U2") (pin "76") (pinfunction "OUTB1_76") (pintype "output"))
      (node (ref "U2") (pin "80") (pinfunction "OUTB1_80") (pintype "output"))
      (node (ref "U2") (pin "EPAD7") (pinfunction "OUTB1_EPAD7") (pintype "output"))
    )
    (net (code "10") (name "Net-(BB-KL)") (class "Default")
      (node (ref "B") (pin "2") (pinfunction "KL_2") (pintype "passive"))
      (node (ref "R7") (pin "2") (pinfunction "2_2") (pintype "passive"))
      (node (ref "U2") (pin "7") (pinfunction "OUTB2_7") (pintype "output"))
      (node (ref "U2") (pin "81") (pinfunction "OUTB2_81") (pintype "output"))
      (node (ref "U2") (pin "85") (pinfunction "OUTB2_85") (pintype "output"))
      (node (ref "U2") (pin "EPAD8") (pinfunction "OUTB2_EPAD8") (pintype "output"))
    )
    (net (code "11") (name "Net-(D1-PadA)") (class "Default")
      (node (ref "D1") (pin "A") (pinfunction "A_A") (pintype "passive"))
      (node (ref "R2") (pin "1") (pinfunction "1_1") (pintype "passive"))
    )
    (net (code "12") (name "Net-(D2-CATHODE)") (class "Default")
      (node (ref "C20") (pin "1") (pinfunction "1_1") (pintype "passive"))
      (node (ref "D2") (pin "1") (pinfunction "CATHODE_1") (pintype "passive"))
      (node (ref "U2") (pin "58") (pinfunction "VCC_58") (pintype "power_in"))
    )
    (net (code "13") (name "Net-(D3-PadA)") (class "Default")
      (node (ref "D3") (pin "A") (pinfunction "A_A") (pintype "passive"))
      (node (ref "R7") (pin "1") (pinfunction "1_1") (pintype "passive"))
    )
    (net (code "14") (name "Net-(D4-A1{slash}K2)") (class "Default")
      (node (ref "C15") (pin "2") (pinfunction "2_2") (pintype "passive"))
      (node (ref "D4") (pin "3") (pinfunction "A1/K2_3") (pintype "passive"))
    )
    (net (code "15") (name "Net-(D4-K1)") (class "Default")
      (node (ref "C18") (pin "2") (pinfunction "2_2") (pintype "passive"))
      (node (ref "D4") (pin "2") (pinfunction "K1_2") (pintype "passive"))
      (node (ref "U2") (pin "56") (pinfunction "VBOOT_56") (pintype "power_in"))
    )
    (net (code "16") (name "Net-(D5-PadA)") (class "Default")
      (node (ref "D5") (pin "A") (pinfunction "A_A") (pintype "passive"))
      (node (ref "R8") (pin "1") (pinfunction "1_1") (pintype "passive"))
    )
    (net (code "17") (name "Net-(D6-PadA)") (class "Default")
      (node (ref "D6") (pin "A") (pinfunction "A_A") (pintype "passive"))
      (node (ref "R9") (pin "1") (pinfunction "1_1") (pintype "passive"))
    )
    (net (code "18") (name "Net-(D7-PadA)") (class "Default")
      (node (ref "D7") (pin "A") (pinfunction "A_A") (pintype "passive"))
      (node (ref "R10") (pin "1") (pinfunction "1_1") (pintype "passive"))
    )
    (net (code "19") (name "Net-(D8-PadA)") (class "Default")
      (node (ref "D8") (pin "A") (pinfunction "A_A") (pintype "passive"))
      (node (ref "R11") (pin "1") (pinfunction "1_1") (pintype "passive"))
    )
    (net (code "20") (name "Net-(D10-PadA)") (class "Default")
      (node (ref "D10") (pin "A") (pinfunction "A_A") (pintype "passive"))
      (node (ref "R15") (pin "1") (pinfunction "1_1") (pintype "passive"))
    )
    (net (code "21") (name "Net-(EMG_SW-Pad1)") (class "Default")
      (node (ref "EMG_SW") (pin "1") (pinfunction "1_1") (pintype "passive"))
      (node (ref "R16") (pin "2") (pinfunction "2_2") (pintype "passive"))
    )
    (net (code "22") (name "Net-(U1-PB14)") (class "Default")
      (node (ref "R2") (pin "2") (pinfunction "2_2") (pintype "passive"))
      (node (ref "U1") (pin "26") (pinfunction "PB14_26") (pintype "bidirectional"))
    )
    (net (code "23") (name "Net-(U1-PF0-OSC_IN)") (class "Default")
      (node (ref "U1") (pin "8") (pinfunction "PF0-OSC_IN_8") (pintype "bidirectional"))
      (node (ref "X1") (pin "P$1") (pinfunction "1_P$1") (pintype "passive"))
    )
    (net (code "24") (name "Net-(U1-PF1-OSC_OUT)") (class "Default")
      (node (ref "U1") (pin "9") (pinfunction "PF1-OSC_OUT_9") (pintype "bidirectional"))
      (node (ref "X1") (pin "P$3") (pinfunction "3_P$3") (pintype "passive"))
    )
    (net (code "25") (name "Net-(U1-PF2-NRST)") (class "Default")
      (node (ref "C1") (pin "2") (pinfunction "2_2") (pintype "passive"))
      (node (ref "R") (pin "1") (pinfunction "1_1") (pintype "passive"))
      (node (ref "U1") (pin "10") (pinfunction "PF2-NRST_10") (pintype "bidirectional"))
    )
    (net (code "26") (name "Net-(U2-ADCIN)") (class "Default")
      (node (ref "C23") (pin "1") (pinfunction "1_1") (pintype "passive"))
      (node (ref "R17") (pin "1") (pinfunction "1_1") (pintype "passive"))
      (node (ref "R18") (pin "2") (pinfunction "2_2") (pintype "passive"))
      (node (ref "U2") (pin "54") (pinfunction "ADCIN_54") (pintype "input"))
    )
    (net (code "27") (name "Net-(U2-CP)") (class "Default")
      (node (ref "C15") (pin "1") (pinfunction "1_1") (pintype "passive"))
      (node (ref "U2") (pin "57") (pinfunction "CP_57") (pintype "output"))
    )
    (net (code "28") (name "Net-(U2-SW)") (class "Default")
      (node (ref "C22") (pin "1") (pinfunction "1_1") (pintype "passive"))
      (node (ref "R16") (pin "1") (pinfunction "1_1") (pintype "passive"))
      (node (ref "U2") (pin "18") (pinfunction "SW_18") (pintype "input"))
    )
    (net (code "29") (name "RESET") (class "Default")
      (node (ref "C8") (pin "1") (pinfunction "1_1") (pintype "passive"))
      (node (ref "U1") (pin "45") (pinfunction "PB6_45") (pintype "bidirectional"))
      (node (ref "U2") (pin "19") (pinfunction "~{STBY}/~{RESET}_19") (pintype "input"))
    )
    (net (code "30") (name "SCK") (class "Default")
      (node (ref "CK") (pin "P$1") (pinfunction "P$1_P$1") (pintype "passive"))
      (node (ref "U1") (pin "42") (pinfunction "PB3_42") (pintype "bidirectional"))
      (node (ref "U2") (pin "11") (pinfunction "CK_11") (pintype "input"))
    )
    (net (code "31") (name "SDI") (class "Default")
      (node (ref "SDI") (pin "P$1") (pinfunction "P$1_P$1") (pintype "passive"))
      (node (ref "U1") (pin "44") (pinfunction "PB5_44") (pintype "bidirectional"))
      (node (ref "U2") (pin "12") (pinfunction "SDI_12") (pintype "input"))
    )
    (net (code "32") (name "SDO") (class "Default")
      (node (ref "SDO") (pin "P$1") (pinfunction "P$1_P$1") (pintype "passive"))
      (node (ref "U1") (pin "43") (pinfunction "PB4_43") (pintype "bidirectional"))
      (node (ref "U2") (pin "14") (pinfunction "SDO_14") (pintype "output"))
    )
    (net (code "33") (name "SENSEA") (class "Default")
      (node (ref "R19") (pin "2") (pinfunction "2_2") (pintype "passive"))
      (node (ref "R20") (pin "2") (pinfunction "2_2") (pintype "passive"))
      (node (ref "R4") (pin "2") (pinfunction "2_2") (pintype "passive"))
      (node (ref "SA_J") (pin "2") (pinfunction "2_2") (pintype "passive"))
      (node (ref "U2") (pin "20") (pinfunction "SENSEA_S_20") (pintype "input"))
      (node (ref "U2") (pin "34") (pinfunction "SENSEA_P_34") (pintype "input"))
      (node (ref "U2") (pin "39") (pinfunction "SENSEA_P_39") (pintype "input"))
    )
    (net (code "34") (name "SENSEB") (class "Default")
      (node (ref "R21") (pin "2") (pinfunction "2_2") (pintype "passive"))
      (node (ref "R22") (pin "2") (pinfunction "2_2") (pintype "passive"))
      (node (ref "R6") (pin "2") (pinfunction "2_2") (pintype "passive"))
      (node (ref "SB_J") (pin "2") (pinfunction "2_2") (pintype "passive"))
      (node (ref "U2") (pin "77") (pinfunction "SENSEB_P_77") (pintype "input"))
      (node (ref "U2") (pin "82") (pinfunction "SENSEB_P_82") (pintype "input"))
      (node (ref "U2") (pin "9") (pinfunction "SENSEB_S_9") (pintype "input"))
    )
    (net (code "35") (name "STCK") (class "Default")
      (node (ref "R5") (pin "1") (pinfunction "1_1") (pintype "passive"))
      (node (ref "U1") (pin "46") (pinfunction "PB7_46") (pintype "bidirectional"))
      (node (ref "U2") (pin "17") (pinfunction "STCK_17") (pintype "input"))
    )
    (net (code "36") (name "USART2_RX") (class "Default")
      (node (ref "U$1") (pin "PAD_PD1") (pinfunction "SD2_PAD_PD1") (pintype "bidirectional"))
      (node (ref "U1") (pin "14") (pinfunction "PA3_14") (pintype "bidirectional"))
    )
    (net (code "37") (name "USART2_TX") (class "Default")
      (node (ref "U$1") (pin "PAD_PU1") (pinfunction "SU2_PAD_PU1") (pintype "bidirectional"))
      (node (ref "U1") (pin "13") (pinfunction "PA2_13") (pintype "bidirectional"))
    )
    (net (code "38") (name "USART3_RX") (class "Default")
      (node (ref "U$1") (pin "PAD_PD2") (pinfunction "SD3_PAD_PD2") (pintype "bidirectional"))
      (node (ref "U1") (pin "23") (pinfunction "PB11_23") (pintype "bidirectional"))
    )
    (net (code "39") (name "USART3_TX") (class "Default")
      (node (ref "U$1") (pin "PAD_PU2") (pinfunction "SU3_PAD_PU2") (pintype "bidirectional"))
      (node (ref "U1") (pin "22") (pinfunction "PB10_22") (pintype "bidirectional"))
    )
    (net (code "40") (name "USART5_RX") (class "Default")
      (node (ref "U$1") (pin "PAD_PD8") (pinfunction "SD4_PAD_PD8") (pintype "bidirectional"))
      (node (ref "U1") (pin "40") (pinfunction "PD2_40") (pintype "bidirectional"))
    )
    (net (code "41") (name "USART5_TX") (class "Default")
      (node (ref "U$1") (pin "PAD_PU8") (pinfunction "SU4_PAD_PU8") (pintype "bidirectional"))
      (node (ref "U1") (pin "41") (pinfunction "PD3_41") (pintype "bidirectional"))
    )
    (net (code "42") (name "USART6_RX") (class "Default")
      (node (ref "U$1") (pin "PAD_PD3") (pinfunction "SD1_PAD_PD3") (pintype "bidirectional"))
      (node (ref "U1") (pin "48") (pinfunction "PB9_48") (pintype "bidirectional"))
    )
    (net (code "43") (name "USART6_TX") (class "Default")
      (node (ref "U$1") (pin "PAD_PU3") (pinfunction "SU1_PAD_PU3") (pintype "bidirectional"))
      (node (ref "U1") (pin "47") (pinfunction "PB8_47") (pintype "bidirectional"))
    )
    (net (code "44") (name "VDD") (class "Default")
      (node (ref "C6") (pin "2") (pinfunction "2_2") (pintype "passive"))
      (node (ref "C7") (pin "1") (pinfunction "+_1") (pintype "passive"))
      (node (ref "FB1") (pin "1") (pinfunction "1_1") (pintype "passive"))
      (node (ref "U$1") (pin "PAD_PU12") (pinfunction "VDD1_PAD_PU12") (pintype "power_in"))
      (node (ref "U$1") (pin "PAD_PU17") (pinfunction "VDD2_PAD_PU17") (pintype "power_in"))
      (node (ref "U$1") (pin "PAD_PU19") (pinfunction "VDD3_PAD_PU19") (pintype "power_in"))
      (node (ref "U1") (pin "31") (pinfunction "VDDIO2_31") (pintype "power_in"))
    )
    (net (code "45") (name "VDDA") (class "Default")
      (node (ref "C16") (pin "2") (pinfunction "2_2") (pintype "passive"))
      (node (ref "C17") (pin "2") (pinfunction "2_2") (pintype "passive"))
      (node (ref "C19") (pin "1") (pinfunction "1_1") (pintype "passive"))
      (node (ref "C2") (pin "2") (pinfunction "2_2") (pintype "passive"))
      (node (ref "C21") (pin "1") (pinfunction "+_1") (pintype "bidirectional"))
      (node (ref "C3") (pin "1") (pinfunction "+_1") (pintype "passive"))
      (node (ref "C4") (pin "2") (pinfunction "2_2") (pintype "passive"))
      (node (ref "C5") (pin "1") (pinfunction "+_1") (pintype "passive"))
      (node (ref "D2") (pin "2") (pinfunction "ANODE_2") (pintype "passive"))
      (node (ref "FB1") (pin "2") (pinfunction "2_2") (pintype "passive"))
      (node (ref "R11") (pin "2") (pinfunction "2_2") (pintype "passive"))
      (node (ref "R13") (pin "2") (pinfunction "2_2") (pintype "passive"))
      (node (ref "R14") (pin "2") (pinfunction "2_2") (pintype "passive"))
      (node (ref "R15") (pin "2") (pinfunction "2_2") (pintype "passive"))
      (node (ref "R5") (pin "2") (pinfunction "2_2") (pintype "passive"))
      (node (ref "U1") (pin "4") (pinfunction "VBAT_4") (pintype "power_in"))
      (node (ref "U1") (pin "5") (pinfunction "VREF+_5") (pintype "power_in"))
      (node (ref "U1") (pin "6") (pinfunction "VDD/VDDA_6") (pintype "power_in"))
      (node (ref "U2") (pin "13") (pinfunction "VDDIO_13") (pintype "power_in"))
      (node (ref "U2") (pin "60") (pinfunction "VCCREG_60") (pintype "power_in"))
      (node (ref "U2") (pin "62") (pinfunction "VREG_62") (pintype "power_in"))
    )
    (net (code "46") (name "VS") (class "Default")
      (node (ref "C10") (pin "1") (pinfunction "+_1") (pintype "passive"))
      (node (ref "C11") (pin "1") (pinfunction "1_1") (pintype "passive"))
      (node (ref "C12") (pin "1") (pinfunction "1_1") (pintype "passive"))
      (node (ref "C13") (pin "1") (pinfunction "1_1") (pintype "passive"))
      (node (ref "C14") (pin "1") (pinfunction "1_1") (pintype "passive"))
      (node (ref "C18") (pin "1") (pinfunction "1_1") (pintype "passive"))
      (node (ref "C9") (pin "1") (pinfunction "+_1") (pintype "passive"))
      (node (ref "D4") (pin "1") (pinfunction "A2_1") (pintype "passive"))
      (node (ref "PWR") (pin "1") (pinfunction "KL_1") (pintype "passive"))
      (node (ref "R17") (pin "2") (pinfunction "2_2") (pintype "passive"))
      (node (ref "U2") (pin "1") (pinfunction "VS_1") (pintype "passive"))
      (node (ref "U2") (pin "23") (pinfunction "VS_23") (pintype "passive"))
      (node (ref "U2") (pin "43") (pinfunction "VS_43") (pintype "passive"))
      (node (ref "U2") (pin "55") (pinfunction "VS_55") (pintype "passive"))
      (node (ref "U2") (pin "61") (pinfunction "VSREG_61") (pintype "power_in"))
      (node (ref "U2") (pin "66") (pinfunction "VS_66") (pintype "passive"))
    )
    (net (code "47") (name "VSSA") (class "Default")
      (node (ref "C10") (pin "2") (pinfunction "-_2") (pintype "passive"))
      (node (ref "C11") (pin "2") (pinfunction "2_2") (pintype "passive"))
      (node (ref "C12") (pin "2") (pinfunction "2_2") (pintype "passive"))
      (node (ref "C13") (pin "2") (pinfunction "2_2") (pintype "passive"))
      (node (ref "C14") (pin "2") (pinfunction "2_2") (pintype "passive"))
      (node (ref "C16") (pin "1") (pinfunction "1_1") (pintype "passive"))
      (node (ref "C17") (pin "1") (pinfunction "1_1") (pintype "passive"))
      (node (ref "C19") (pin "2") (pinfunction "2_2") (pintype "passive"))
      (node (ref "C2") (pin "1") (pinfunction "1_1") (pintype "passive"))
      (node (ref "C20") (pin "2") (pinfunction "2_2") (pintype "passive"))
      (node (ref "C21") (pin "2") (pinfunction "-_2") (pintype "bidirectional"))
      (node (ref "C22") (pin "2") (pinfunction "2_2") (pintype "passive"))
      (node (ref "C23") (pin "2") (pinfunction "2_2") (pintype "passive"))
      (node (ref "C3") (pin "2") (pinfunction "-_2") (pintype "passive"))
      (node (ref "C4") (pin "1") (pinfunction "1_1") (pintype "passive"))
      (node (ref "C5") (pin "2") (pinfunction "-_2") (pintype "passive"))
      (node (ref "C8") (pin "2") (pinfunction "2_2") (pintype "passive"))
      (node (ref "C9") (pin "2") (pinfunction "-_2") (pintype "passive"))
      (node (ref "D3") (pin "C") (pinfunction "C_C") (pintype "passive"))
      (node (ref "D5") (pin "C") (pinfunction "C_C") (pintype "passive"))
      (node (ref "D6") (pin "C") (pinfunction "C_C") (pintype "passive"))
      (node (ref "D7") (pin "C") (pinfunction "C_C") (pintype "passive"))
      (node (ref "EMG_SW") (pin "2") (pinfunction "2_2") (pintype "passive"))
      (node (ref "PWR") (pin "2") (pinfunction "KL_2") (pintype "passive"))
      (node (ref "R1") (pin "2") (pinfunction "2_2") (pintype "passive"))
      (node (ref "R18") (pin "1") (pinfunction "1_1") (pintype "passive"))
      (node (ref "R19") (pin "1") (pinfunction "1_1") (pintype "passive"))
      (node (ref "R20") (pin "1") (pinfunction "1_1") (pintype "passive"))
      (node (ref "R21") (pin "1") (pinfunction "1_1") (pintype "passive"))
      (node (ref "R22") (pin "1") (pinfunction "1_1") (pintype "passive"))
      (node (ref "R4") (pin "1") (pinfunction "1_1") (pintype "passive"))
      (node (ref "R6") (pin "1") (pinfunction "1_1") (pintype "passive"))
      (node (ref "SA_J") (pin "1") (pinfunction "1_1") (pintype "passive"))
      (node (ref "SB_J") (pin "1") (pinfunction "1_1") (pintype "passive"))
      (node (ref "U1") (pin "7") (pinfunction "VSS/VSSA_7") (pintype "passive"))
      (node (ref "U2") (pin "21") (pinfunction "GND_21") (pintype "output"))
      (node (ref "U2") (pin "59") (pinfunction "GND_59") (pintype "output"))
      (node (ref "U2") (pin "8") (pinfunction "GND_8") (pintype "output"))
      (node (ref "U2") (pin "EPAD9") (pinfunction "GND_EPAD9") (pintype "output"))
    )
    (net (code "48") (name "unconnected-(U1-PA0-Pad11)") (class "Default")
      (node (ref "U1") (pin "11") (pinfunction "PA0_11") (pintype "bidirectional"))
    )
    (net (code "49") (name "unconnected-(U1-PA1-Pad12)") (class "Default")
      (node (ref "U1") (pin "12") (pinfunction "PA1_12") (pintype "bidirectional"))
    )
    (net (code "50") (name "unconnected-(U1-PA4-Pad15)") (class "Default")
      (node (ref "U1") (pin "15") (pinfunction "PA4_15") (pintype "bidirectional"))
    )
    (net (code "51") (name "unconnected-(U1-PA5-Pad16)") (class "Default")
      (node (ref "U1") (pin "16") (pinfunction "PA5_16") (pintype "bidirectional"))
    )
    (net (code "52") (name "unconnected-(U1-PA6-Pad17)") (class "Default")
      (node (ref "U1") (pin "17") (pinfunction "PA6_17") (pintype "bidirectional"))
    )
    (net (code "53") (name "unconnected-(U1-PA7-Pad18)") (class "Default")
      (node (ref "U1") (pin "18") (pinfunction "PA7_18") (pintype "bidirectional"))
    )
    (net (code "54") (name "unconnected-(U1-PA8-Pad28)") (class "Default")
      (node (ref "U1") (pin "28") (pinfunction "PA8_28") (pintype "bidirectional"))
    )
    (net (code "55") (name "unconnected-(U1-PA9-Pad29)") (class "Default")
      (node (ref "U1") (pin "29") (pinfunction "PA9_29") (pintype "bidirectional"))
    )
    (net (code "56") (name "unconnected-(U1-PA10-Pad32)") (class "Default")
      (node (ref "U1") (pin "32") (pinfunction "PA10_32") (pintype "bidirectional"))
    )
    (net (code "57") (name "unconnected-(U1-PB0-Pad19)") (class "Default")
      (node (ref "U1") (pin "19") (pinfunction "PB0_19") (pintype "bidirectional"))
    )
    (net (code "58") (name "unconnected-(U1-PB1-Pad20)") (class "Default")
      (node (ref "U1") (pin "20") (pinfunction "PB1_20") (pintype "bidirectional"))
    )
    (net (code "59") (name "unconnected-(U1-PB2-Pad21)") (class "Default")
      (node (ref "U1") (pin "21") (pinfunction "PB2_21") (pintype "bidirectional"))
    )
    (net (code "60") (name "unconnected-(U1-PB12-Pad24)") (class "Default")
      (node (ref "U1") (pin "24") (pinfunction "PB12_24") (pintype "bidirectional"))
    )
    (net (code "61") (name "unconnected-(U1-PB13-Pad25)") (class "Default")
      (node (ref "U1") (pin "25") (pinfunction "PB13_25") (pintype "bidirectional"))
    )
    (net (code "62") (name "unconnected-(U1-PB15-Pad27)") (class "Default")
      (node (ref "U1") (pin "27") (pinfunction "PB15_27") (pintype "bidirectional"))
    )
    (net (code "63") (name "unconnected-(U1-PC13-Pad1)") (class "Default")
      (node (ref "U1") (pin "1") (pinfunction "PC13_1") (pintype "bidirectional"))
    )
    (net (code "64") (name "unconnected-(U1-PC14-OSC32_IN-Pad2)") (class "Default")
      (node (ref "U1") (pin "2") (pinfunction "PC14-OSC32_IN_2") (pintype "bidirectional"))
    )
    (net (code "65") (name "unconnected-(U1-PC15-OSC32_OUT-Pad3)") (class "Default")
      (node (ref "U1") (pin "3") (pinfunction "PC15-OSC32_OUT_3") (pintype "bidirectional"))
    )
    (net (code "66") (name "unconnected-(U1-PD0-Pad38)") (class "Default")
      (node (ref "U1") (pin "38") (pinfunction "PD0_38") (pintype "bidirectional"))
    )
    (net (code "67") (name "unconnected-(U1-PD1-Pad39)") (class "Default")
      (node (ref "U1") (pin "39") (pinfunction "PD1_39") (pintype "bidirectional"))
    )
    (net (code "68") (name "unconnected-(U2-OSCIN-Pad63)") (class "Default")
      (node (ref "U2") (pin "63") (pinfunction "OSCIN_63") (pintype "input"))
    )
    (net (code "69") (name "unconnected-(U2-OSCOUT-Pad64)") (class "Default")
      (node (ref "U2") (pin "64") (pinfunction "OSCOUT_64") (pintype "output"))
    )
  )
)
